# 105358-3SC001-03_IO_BRD.net
KiCad netlist of a schematic drawn in Altium Designer
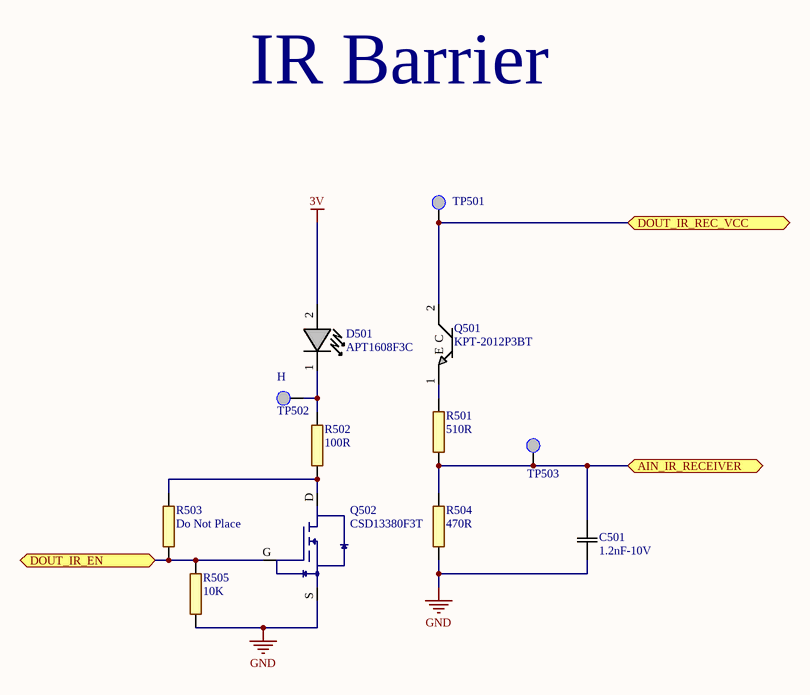
[diagram p0: 105358-3SC001-03_IO_BRD.SchDoc]

(export (version "E")
  (design (tool "Eeschema 10.0.6"))
  (components
    (comp (ref "C501")
      (value "1.2nF-10V")
      (footprint "0402C_HIGH_DENSITY")
      (description "1.2nF ±10% 10V U2J Ceramic Capacitor 0402")
      (fields
        (field (name "MANUFACTURER PART NUMBER") "GRM1557U1A122JA01D")
        (field (name "MANUFACTURER") "Murata Electronics North America")
      )
      (libsource (lib "ConnectMedical") (part "0402C-1.2nF-10V"))
    )
    (comp (ref "D501")
      (value "APT1608F3C")
      (footprint "APT1608F3C")
      (description "0603 INFRARED DIODE")
      (fields
        (field (name "MANUFACTURER") "Kingbright")
        (field (name "DIGI-KEY PART NUMBER") "754-1433-1-ND")
      )
      (libsource (lib "ConnectMedical") (part "APT1608F3C"))
    )
    (comp (ref "Q501")
      (value "KPT-2012P3BT")
      (footprint "APT2012P3BT")
      (description "0805 PHOTOTRANSISTOR")
      (fields
        (field (name "MANUFACTURER") "Kingbright")
        (field (name "DIGI-KEY PART NUMBER") "754-1436-1-ND")
      )
      (libsource (lib "ConnectMedical") (part "APT2012P3BT"))
    )
    (comp (ref "Q502")
      (value "CSD13380F3T")
      (footprint "CSD13380F3-DFN40P69X35-3L")
      (description "12V N-CHANNEL FEMTOFET MOSFET")
      (fields (field (name "MANUFACTURER") "Texas Instruments"))
      (libsource (lib "ConnectMedical") (part "CSD13380F3T"))
    )
    (comp (ref "R501")
      (value "510R")
      (footprint "0402R-GENERIC")
      (description "RES SMD 510OHM 1% 1/16W 0402")
      (fields (field (name "POWER") "0.063W") (field (name "TOLERANCE") "1%"))
      (libsource (lib "ConnectMedical") (part "0402R-510 OHM-1%-0.063W"))
    )
    (comp (ref "R502")
      (value "100R")
      (footprint "0402R-GENERIC")
      (description "RES SMD 100OHM 1% 1/16W 0402")
      (fields (field (name "DIGI-KEY PART NUMBER") "311-100LRCT-ND") (field (name "MANUFACTURER") "Yageo"))
      (libsource (lib "ConnectMedical") (part "0402R-100 OHM-1%-0.063W"))
    )
    (comp (ref "R503")
      (value "Do Not Place")
      (footprint "0402R-GENERIC - DNP")
      (libsource (lib "ConnectMedical") (part "0402R-Do Not Place"))
    )
    (comp (ref "R504")
      (value "470R")
      (footprint "0402R-GENERIC")
      (description "RES SMD 470 OHM 1% 1/16W 0402")
      (fields (field (name "TOLERANCE") "1%") (field (name "POWER") "0.063W"))
      (libsource (lib "ConnectMedical") (part "0402R-470 OHM-1%-0.063W"))
    )
    (comp (ref "R505")
      (value "10K")
      (footprint "0402R-GENERIC")
      (description "RES SMD 10kOHM 1% 1/16W 0402")
      (fields (field (name "DIGI-KEY PART NUMBER") "311-10.0KLRCT-ND") (field (name "MANUFACTURER") "Yageo"))
      (libsource (lib "ConnectMedical") (part "0402R-10k OHM-1%-0.063W"))
    )
    (comp (ref "TP501")
      (value "TEST POINT")
      (footprint "PAD TEST POINT")
      (description "Testing Poiny")
      (libsource (lib "ConnectMedical") (part "TEST POINT"))
    )
    (comp (ref "TP502")
      (value "TEST POINT")
      (footprint "PAD TEST POINT")
      (description "Testing Poiny")
      (libsource (lib "ConnectMedical") (part "TEST POINT"))
    )
    (comp (ref "TP503")
      (value "TEST POINT")
      (footprint "PAD TEST POINT")
      (description "Testing Poiny")
      (libsource (lib "ConnectMedical") (part "TEST POINT"))
    )
  )
  (nets
    (net (code "1") (name "/AIN_IR_RECEIVER") (class "Default")
      (node (ref "C501") (pin "2") (pinfunction "2_2") (pintype "passive"))
      (node (ref "R501") (pin "2") (pintype "passive"))
      (node (ref "R504") (pin "1") (pintype "passive"))
      (node (ref "TP503") (pin "1") (pinfunction "Test_Point_1") (pintype "passive"))
    )
    (net (code "2") (name "/DOUT_IR_EN") (class "Default")
      (node (ref "Q502") (pin "G") (pinfunction "1_G") (pintype "passive"))
      (node (ref "R503") (pin "2") (pintype "passive"))
      (node (ref "R505") (pin "1") (pintype "passive"))
    )
    (net (code "3") (name "/DOUT_IR_REC_VCC") (class "Default")
      (node (ref "Q501") (pin "2") (pinfunction "C_2") (pintype "passive"))
      (node (ref "TP501") (pin "1") (pinfunction "Test_Point_1") (pintype "passive"))
    )
    (net (code "4") (name "3V") (class "Default")
      (node (ref "D501") (pin "2") (pinfunction "2_2") (pintype "passive"))
    )
    (net (code "5") (name "GND") (class "Default")
      (node (ref "C501") (pin "1") (pinfunction "1_1") (pintype "passive"))
      (node (ref "Q502") (pin "S") (pinfunction "2_S") (pintype "passive"))
      (node (ref "R504") (pin "2") (pintype "passive"))
      (node (ref "R505") (pin "2") (pintype "passive"))
    )
    (net (code "6") (name "Net-(D501-K)") (class "Default")
      (node (ref "D501") (pin "1") (pinfunction "K_1") (pintype "passive"))
      (node (ref "R502") (pin "1") (pintype "passive"))
      (node (ref "TP502") (pin "1") (pinfunction "Test_Point_1") (pintype "passive"))
    )
    (net (code "7") (name "Net-(Q501-E)") (class "Default")
      (node (ref "Q501") (pin "1") (pinfunction "E_1") (pintype "passive"))
      (node (ref "R501") (pin "1") (pintype "passive"))
    )
    (net (code "8") (name "Net-(Q502-3)") (class "Default")
      (node (ref "Q502") (pin "D") (pinfunction "3_D") (pintype "passive"))
      (node (ref "R502") (pin "2") (pintype "passive"))
      (node (ref "R503") (pin "1") (pintype "passive"))
    )
  )
)
